# Proto.net
KiCad netlist of a schematic drawn in EAGLE
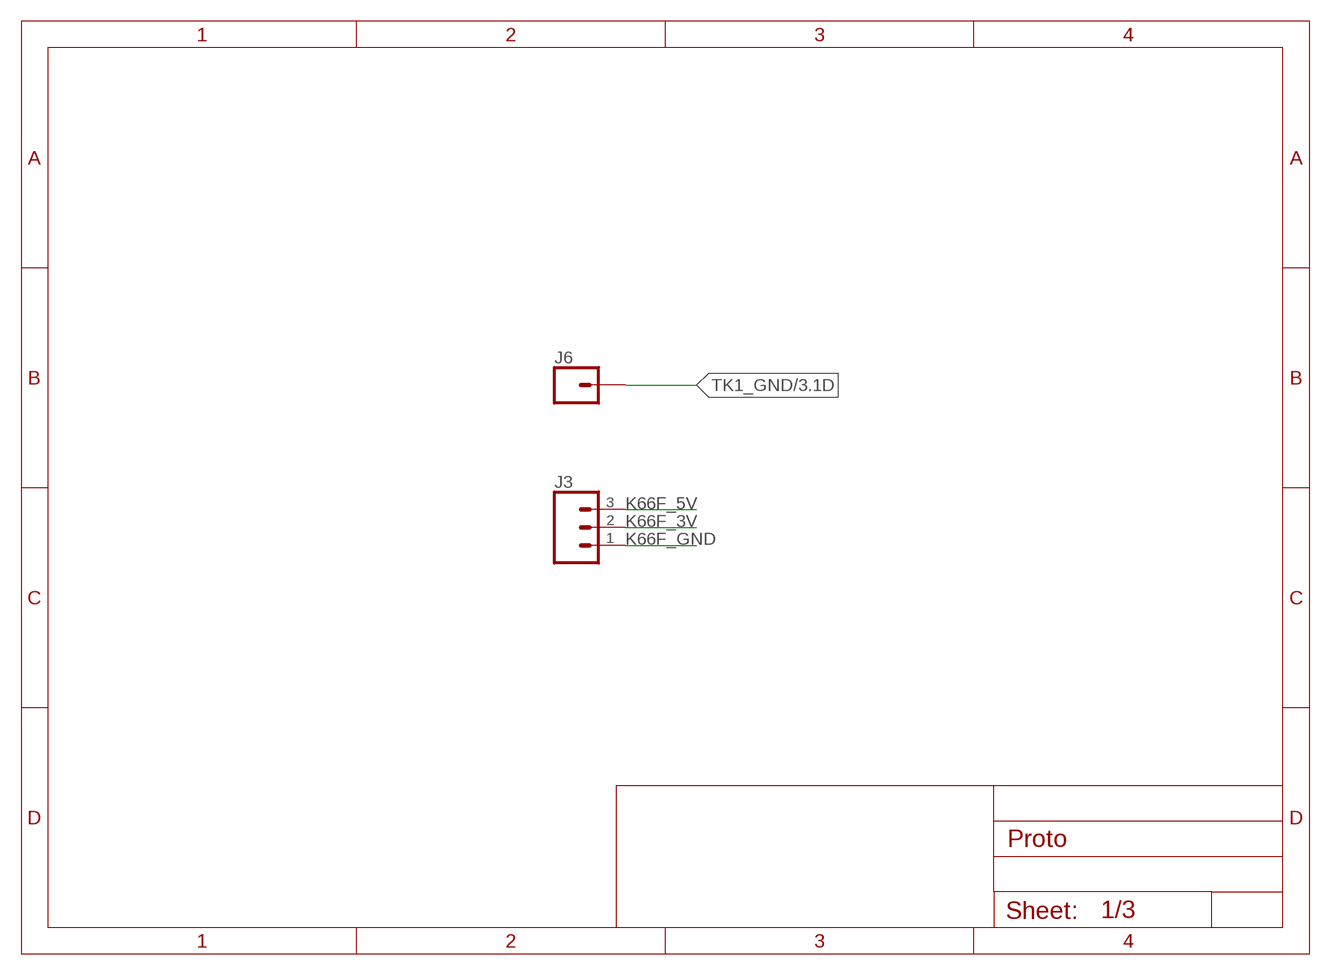
[diagram p0: schematic, sheet 1]
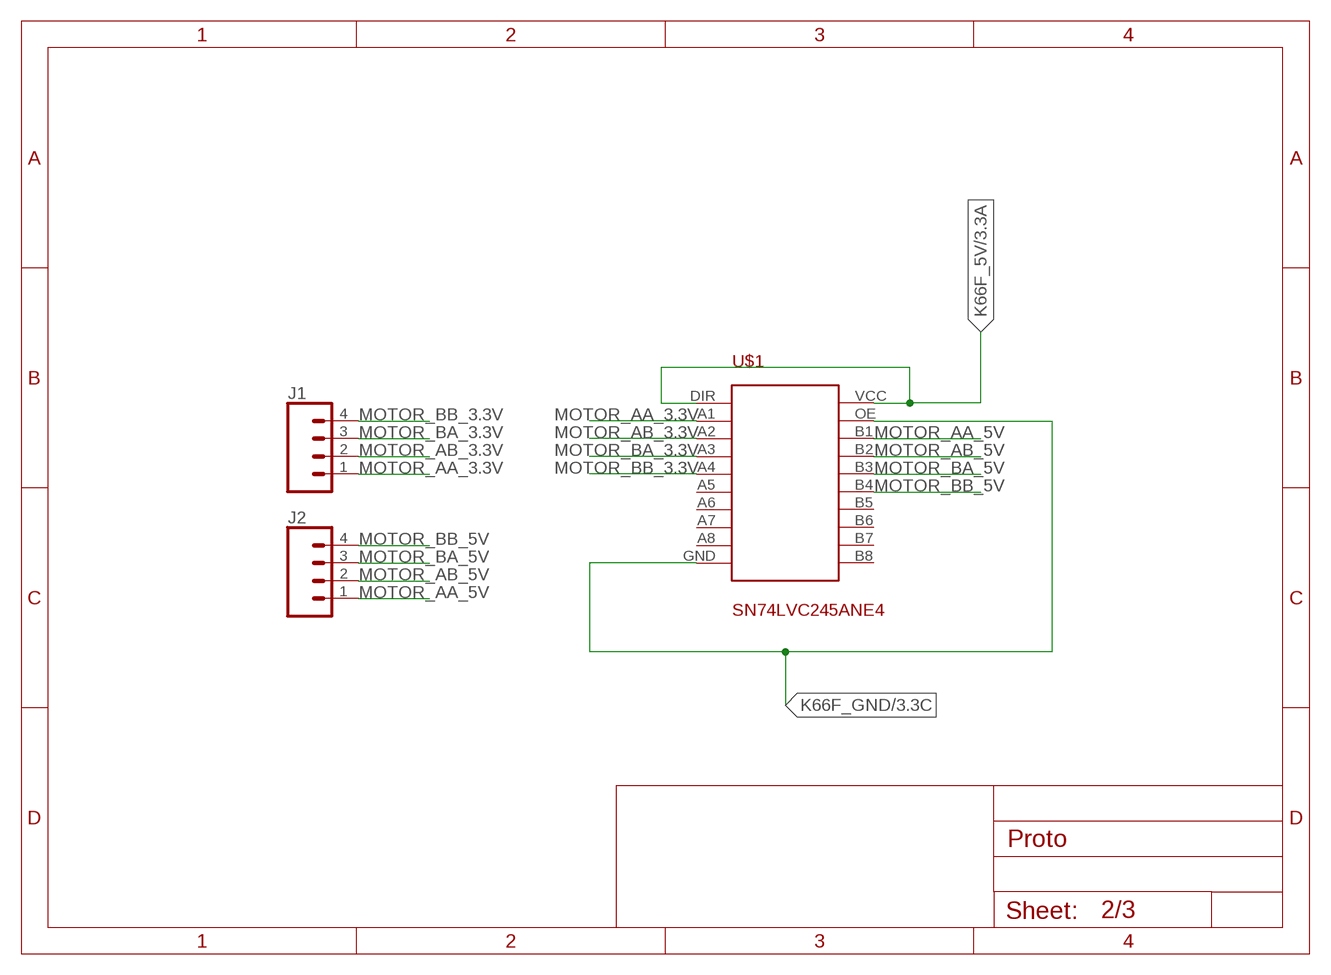
[diagram p1: schematic, sheet 2]
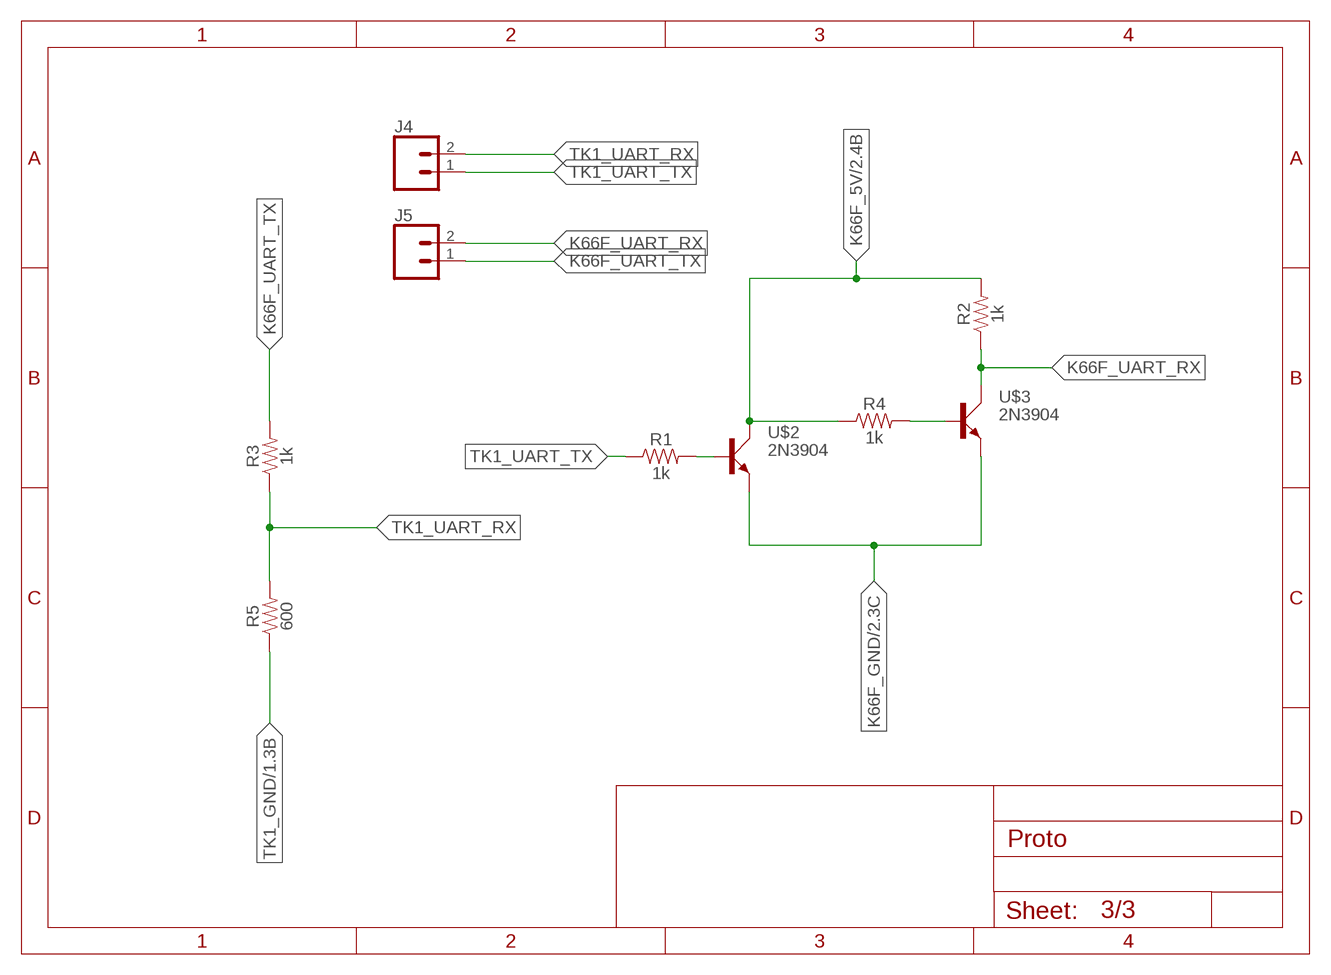
[diagram p2: schematic, sheet 3]

(export (version "E")
  (design (tool "Eeschema 10.0.6"))
  (components
    (comp (ref "J4")
      (value "CONN_02LOCK")
      (footprint "eagle-import:1X02_LOCK")
      (libsource (lib "eagle-import") (part "CONN_02LOCK"))
    )
    (comp (ref "J5")
      (value "CONN_02LOCK")
      (footprint "eagle-import:1X02_LOCK")
      (libsource (lib "eagle-import") (part "CONN_02LOCK"))
    )
    (comp (ref "R1")
      (value "1k")
      (footprint "eagle-import:AXIAL-0.3")
      (libsource (lib "eagle-import") (part "1KOHM-HORIZ-1/4W-5%"))
    )
    (comp (ref "R2")
      (value "1k")
      (footprint "eagle-import:AXIAL-0.3")
      (libsource (lib "eagle-import") (part "1KOHM-HORIZ-1/4W-5%"))
    )
    (comp (ref "R3")
      (value "1k")
      (footprint "eagle-import:AXIAL-0.3")
      (libsource (lib "eagle-import") (part "1KOHM-HORIZ-1/4W-5%"))
    )
    (comp (ref "R4")
      (value "1k")
      (footprint "eagle-import:AXIAL-0.3")
      (libsource (lib "eagle-import") (part "1KOHM-HORIZ-1/4W-5%"))
    )
    (comp (ref "R5")
      (value "600")
      (footprint "eagle-import:AXIAL-0.3")
      (libsource (lib "eagle-import") (part "1KOHM-HORIZ-1/4W-5%"))
    )
    (comp (ref "U$2")
      (value "2N3904")
      (footprint "eagle-import:2N3904_BENT")
      (libsource (lib "eagle-import") (part "2N3904"))
    )
    (comp (ref "U$3")
      (value "2N3904")
      (footprint "eagle-import:2N3904_BENT")
      (libsource (lib "eagle-import") (part "2N3904"))
    )
    (comp (ref "J3")
      (value "CONN_03LOCK")
      (footprint "eagle-import:1X03_LOCK")
      (libsource (lib "eagle-import") (part "CONN_03LOCK"))
    )
    (comp (ref "J6")
      (value "CONN_01")
      (footprint "eagle-import:1X01")
      (libsource (lib "eagle-import") (part "CONN_01"))
    )
    (comp (ref "J1")
      (value "CONN_04LOCK")
      (footprint "eagle-import:1X04_LOCK")
      (libsource (lib "eagle-import") (part "CONN_04LOCK"))
    )
    (comp (ref "J2")
      (value "CONN_04LOCK")
      (footprint "eagle-import:1X04_LOCK")
      (libsource (lib "eagle-import") (part "CONN_04LOCK"))
    )
    (comp (ref "U$1")
      (value "SN74LVC245ANE4")
      (footprint "eagle-import:SN74LVC245ANE4")
      (libsource (lib "eagle-import") (part "SN74LVC245ANE4"))
    )
  )
  (nets
    (net (code "1") (name "K66F_3V") (class "Default")
      (node (ref "J3") (pin "2") (pinfunction "2_2") (pintype "passive"))
    )
    (net (code "2") (name "K66F_5V") (class "Default")
      (node (ref "J3") (pin "3") (pinfunction "3_3") (pintype "passive"))
      (node (ref "R2") (pin "P$2") (pinfunction "2_P$2") (pintype "passive"))
      (node (ref "R4") (pin "P$1") (pinfunction "1_P$1") (pintype "passive"))
      (node (ref "U$1") (pin "DIR") (pinfunction "DIR_DIR") (pintype "input"))
      (node (ref "U$1") (pin "VCC") (pinfunction "VCC_VCC") (pintype "passive"))
      (node (ref "U$2") (pin "C") (pinfunction "C_C") (pintype "passive"))
    )
    (net (code "3") (name "K66F_GND") (class "Default")
      (node (ref "J3") (pin "1") (pinfunction "1_1") (pintype "passive"))
      (node (ref "U$1") (pin "GND") (pinfunction "GND_GND") (pintype "passive"))
      (node (ref "U$1") (pin "OE") (pinfunction "OE_OE") (pintype "input"))
      (node (ref "U$2") (pin "E") (pinfunction "E_E") (pintype "passive"))
      (node (ref "U$3") (pin "E") (pinfunction "E_E") (pintype "passive"))
    )
    (net (code "4") (name "K66F_UART_RX") (class "Default")
      (node (ref "J5") (pin "2") (pinfunction "2_2") (pintype "passive"))
      (node (ref "R2") (pin "P$1") (pinfunction "1_P$1") (pintype "passive"))
      (node (ref "U$3") (pin "C") (pinfunction "C_C") (pintype "passive"))
    )
    (net (code "5") (name "K66F_UART_TX") (class "Default")
      (node (ref "J5") (pin "1") (pinfunction "1_1") (pintype "passive"))
      (node (ref "R3") (pin "P$2") (pinfunction "2_P$2") (pintype "passive"))
    )
    (net (code "6") (name "MOTOR_AA_3.3V") (class "Default")
      (node (ref "J1") (pin "1") (pinfunction "1_1") (pintype "passive"))
      (node (ref "U$1") (pin "A1") (pinfunction "A1_A1") (pintype "bidirectional"))
    )
    (net (code "7") (name "MOTOR_AA_5V") (class "Default")
      (node (ref "J2") (pin "1") (pinfunction "1_1") (pintype "passive"))
      (node (ref "U$1") (pin "B1") (pinfunction "B1_B1") (pintype "bidirectional"))
    )
    (net (code "8") (name "MOTOR_AB_3.3V") (class "Default")
      (node (ref "J1") (pin "2") (pinfunction "2_2") (pintype "passive"))
      (node (ref "U$1") (pin "A2") (pinfunction "A2_A2") (pintype "bidirectional"))
    )
    (net (code "9") (name "MOTOR_AB_5V") (class "Default")
      (node (ref "J2") (pin "2") (pinfunction "2_2") (pintype "passive"))
      (node (ref "U$1") (pin "B2") (pinfunction "B2_B2") (pintype "bidirectional"))
    )
    (net (code "10") (name "MOTOR_BA_3.3V") (class "Default")
      (node (ref "J1") (pin "3") (pinfunction "3_3") (pintype "passive"))
      (node (ref "U$1") (pin "A3") (pinfunction "A3_A3") (pintype "bidirectional"))
    )
    (net (code "11") (name "MOTOR_BA_5V") (class "Default")
      (node (ref "J2") (pin "3") (pinfunction "3_3") (pintype "passive"))
      (node (ref "U$1") (pin "B3") (pinfunction "B3_B3") (pintype "bidirectional"))
    )
    (net (code "12") (name "MOTOR_BB_3.3V") (class "Default")
      (node (ref "J1") (pin "4") (pinfunction "4_4") (pintype "passive"))
      (node (ref "U$1") (pin "A4") (pinfunction "A4_A4") (pintype "bidirectional"))
    )
    (net (code "13") (name "MOTOR_BB_5V") (class "Default")
      (node (ref "J2") (pin "4") (pinfunction "4_4") (pintype "passive"))
      (node (ref "U$1") (pin "B4") (pinfunction "B4_B4") (pintype "bidirectional"))
    )
    (net (code "14") (name "Net-(R1-2)") (class "Default")
      (node (ref "R1") (pin "P$2") (pinfunction "2_P$2") (pintype "passive"))
      (node (ref "U$2") (pin "B") (pinfunction "B_B") (pintype "passive"))
    )
    (net (code "15") (name "Net-(R4-2)") (class "Default")
      (node (ref "R4") (pin "P$2") (pinfunction "2_P$2") (pintype "passive"))
      (node (ref "U$3") (pin "B") (pinfunction "B_B") (pintype "passive"))
    )
    (net (code "16") (name "TK1_GND") (class "Default")
      (node (ref "J6") (pin "1") (pinfunction "1_1") (pintype "passive"))
      (node (ref "R5") (pin "P$1") (pinfunction "1_P$1") (pintype "passive"))
    )
    (net (code "17") (name "TK1_UART_RX") (class "Default")
      (node (ref "J4") (pin "2") (pinfunction "2_2") (pintype "passive"))
      (node (ref "R3") (pin "P$1") (pinfunction "1_P$1") (pintype "passive"))
      (node (ref "R5") (pin "P$2") (pinfunction "2_P$2") (pintype "passive"))
    )
    (net (code "18") (name "TK1_UART_TX") (class "Default")
      (node (ref "J4") (pin "1") (pinfunction "1_1") (pintype "passive"))
      (node (ref "R1") (pin "P$1") (pinfunction "1_P$1") (pintype "passive"))
    )
    (net (code "19") (name "unconnected-(U$1-PadA5)") (class "Default")
      (node (ref "U$1") (pin "A5") (pinfunction "A5_A5") (pintype "bidirectional"))
    )
    (net (code "20") (name "unconnected-(U$1-PadA6)") (class "Default")
      (node (ref "U$1") (pin "A6") (pinfunction "A6_A6") (pintype "bidirectional"))
    )
    (net (code "21") (name "unconnected-(U$1-PadA7)") (class "Default")
      (node (ref "U$1") (pin "A7") (pinfunction "A7_A7") (pintype "bidirectional"))
    )
    (net (code "22") (name "unconnected-(U$1-PadA8)") (class "Default")
      (node (ref "U$1") (pin "A8") (pinfunction "A8_A8") (pintype "bidirectional"))
    )
    (net (code "23") (name "unconnected-(U$1-PadB5)") (class "Default")
      (node (ref "U$1") (pin "B5") (pinfunction "B5_B5") (pintype "bidirectional"))
    )
    (net (code "24") (name "unconnected-(U$1-PadB6)") (class "Default")
      (node (ref "U$1") (pin "B6") (pinfunction "B6_B6") (pintype "bidirectional"))
    )
    (net (code "25") (name "unconnected-(U$1-PadB7)") (class "Default")
      (node (ref "U$1") (pin "B7") (pinfunction "B7_B7") (pintype "bidirectional"))
    )
    (net (code "26") (name "unconnected-(U$1-PadB8)") (class "Default")
      (node (ref "U$1") (pin "B8") (pinfunction "B8_B8") (pintype "bidirectional"))
    )
  )
)
